# dsPIC_I2CMini.net
KiCad netlist of a schematic drawn in EAGLE
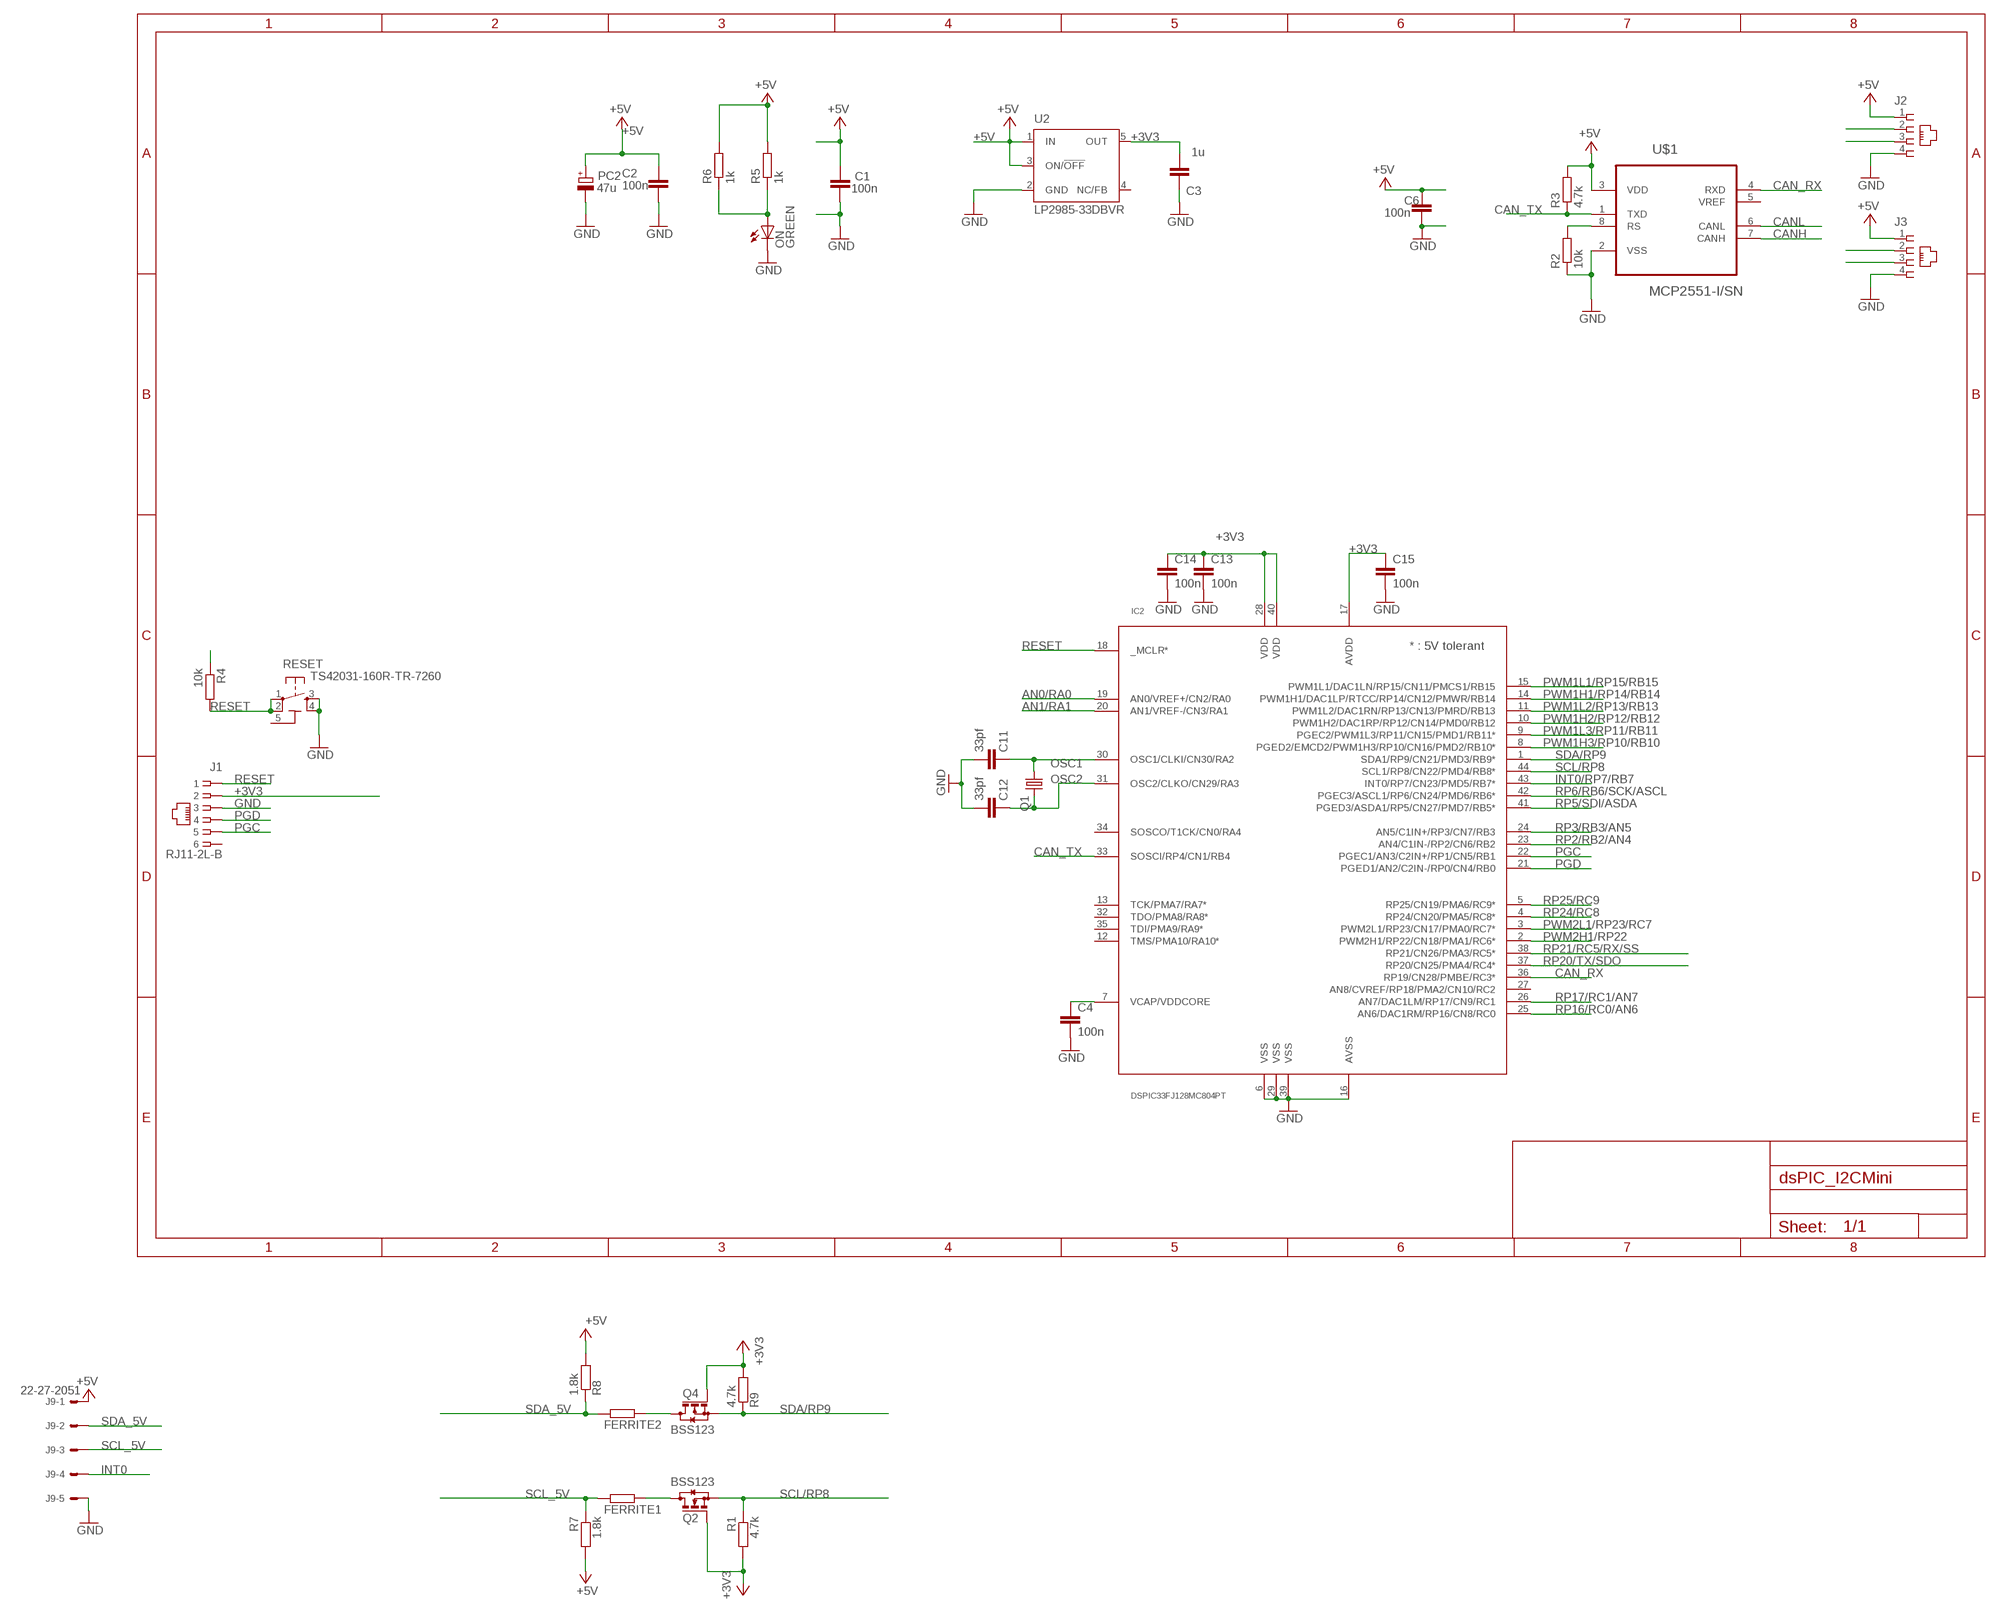
[diagram p0: schematic, sheet 1]

(export (version "E")
  (design (tool "Eeschema 10.0.6"))
  (components
    (comp (ref "C1")
      (value "100n")
      (footprint "eagle-import:C0603-ROUND")
      (libsource (lib "eagle-import") (part "C-EU0603-RND"))
    )
    (comp (ref "C2")
      (value "100n")
      (footprint "eagle-import:C0603-ROUND")
      (libsource (lib "eagle-import") (part "C-EU0603-RND"))
    )
    (comp (ref "C3")
      (value "1u")
      (footprint "eagle-import:C0603-ROUND")
      (libsource (lib "eagle-import") (part "C-EU0603-RND"))
    )
    (comp (ref "C4")
      (value "100n")
      (footprint "eagle-import:C0603K")
      (libsource (lib "eagle-import") (part "SmartPrj_C-EUC0603K"))
    )
    (comp (ref "C6")
      (value "100n")
      (footprint "eagle-import:C0603K")
      (libsource (lib "eagle-import") (part "SmartPrj_C-EUC0603K"))
    )
    (comp (ref "C11")
      (value "33pf")
      (footprint "eagle-import:C0603")
      (libsource (lib "eagle-import") (part "C-EUC0603"))
    )
    (comp (ref "C12")
      (value "33pf")
      (footprint "eagle-import:C0603")
      (libsource (lib "eagle-import") (part "C-EUC0603"))
    )
    (comp (ref "C13")
      (value "100n")
      (footprint "eagle-import:C0603")
      (libsource (lib "eagle-import") (part "C-EUC0603"))
    )
    (comp (ref "C14")
      (value "100n")
      (footprint "eagle-import:C0603")
      (libsource (lib "eagle-import") (part "C-EUC0603"))
    )
    (comp (ref "C15")
      (value "100n")
      (footprint "eagle-import:C0603")
      (libsource (lib "eagle-import") (part "C-EUC0603"))
    )
    (comp (ref "FERRITE1")
      (value "R-EU_M0805")
      (footprint "eagle-import:M0805")
      (libsource (lib "eagle-import") (part "R-EU_M0805"))
    )
    (comp (ref "FERRITE2")
      (value "R-EU_M0805")
      (footprint "eagle-import:M0805")
      (libsource (lib "eagle-import") (part "R-EU_M0805"))
    )
    (comp (ref "IC2")
      (value "DSPIC33FJ128MC804PT")
      (footprint "eagle-import:TQFP44")
      (libsource (lib "eagle-import") (part "DSPIC33F04PTJ128MC8"))
    )
    (comp (ref "J1")
      (value "RJ11-2L-B")
      (footprint "eagle-import:RJ11-NO_SHIELD")
      (fields (field (name "MF") "TYCO ELECTRONICS") (field (name "OC_FARNELL") "1393306"))
      (libsource (lib "eagle-import") (part "RJ11-2L-B"))
    )
    (comp (ref "J2")
      (value "520249-2")
      (footprint "eagle-import:520249-2")
      (libsource (lib "eagle-import") (part "520249-2"))
    )
    (comp (ref "J3")
      (value "520249-2")
      (footprint "eagle-import:520249-2")
      (libsource (lib "eagle-import") (part "520249-2"))
    )
    (comp (ref "J9")
      (value "22-27-2051")
      (footprint "eagle-import:6410-05")
      (libsource (lib "eagle-import") (part "22-?-0527-2051"))
    )
    (comp (ref "ON")
      (value "GREEN")
      (footprint "eagle-import:CHIP-LED0805")
      (libsource (lib "eagle-import") (part "LEDCHIP-LED0805"))
    )
    (comp (ref "PC2")
      (value "47u")
      (footprint "eagle-import:PANASONIC_D")
      (libsource (lib "eagle-import") (part "CPOL-EUD"))
    )
    (comp (ref "Q1")
      (value "CRYSTALSM49")
      (footprint "eagle-import:SM49")
      (fields (field (name "OC_FARNELL") "1842332"))
      (libsource (lib "eagle-import") (part "CRYSTALSM49"))
    )
    (comp (ref "Q2")
      (value "BSS123")
      (footprint "eagle-import:SOT23")
      (libsource (lib "eagle-import") (part "BSS123"))
    )
    (comp (ref "Q4")
      (value "BSS123")
      (footprint "eagle-import:SOT23")
      (libsource (lib "eagle-import") (part "BSS123"))
    )
    (comp (ref "R1")
      (value "4.7k")
      (footprint "eagle-import:R0805")
      (libsource (lib "eagle-import") (part "rcl_R-EU_R0805"))
    )
    (comp (ref "R2")
      (value "10k")
      (footprint "eagle-import:R0805")
      (libsource (lib "eagle-import") (part "R-EU_R0805"))
    )
    (comp (ref "R3")
      (value "4.7k")
      (footprint "eagle-import:R0805")
      (libsource (lib "eagle-import") (part "R-EU_R0805"))
    )
    (comp (ref "R4")
      (value "10k")
      (footprint "eagle-import:R0805")
      (libsource (lib "eagle-import") (part "R-EU_R0805"))
    )
    (comp (ref "R5")
      (value "1k")
      (footprint "eagle-import:R0805")
      (libsource (lib "eagle-import") (part "R-EU_R0805"))
    )
    (comp (ref "R6")
      (value "1k")
      (footprint "eagle-import:R0805")
      (libsource (lib "eagle-import") (part "R-EU_R0805"))
    )
    (comp (ref "R7")
      (value "1.8k")
      (footprint "eagle-import:R0805")
      (libsource (lib "eagle-import") (part "rcl_R-EU_R0805"))
    )
    (comp (ref "R8")
      (value "1.8k")
      (footprint "eagle-import:R0805")
      (libsource (lib "eagle-import") (part "rcl_R-EU_R0805"))
    )
    (comp (ref "R9")
      (value "4.7k")
      (footprint "eagle-import:R0805")
      (libsource (lib "eagle-import") (part "rcl_R-EU_R0805"))
    )
    (comp (ref "RESET")
      (value "TS42031-160R-TR-7260")
      (footprint "eagle-import:TS42")
      (libsource (lib "eagle-import") (part "TS42"))
    )
    (comp (ref "U$1")
      (value "MCP2551-I/SN")
      (footprint "eagle-import:SOIC127P600X175-8N")
      (libsource (lib "eagle-import") (part "MCP2551-I/SN"))
    )
    (comp (ref "U2")
      (value "LP2985-33DBVR")
      (footprint "eagle-import:SOT23-DBV")
      (libsource (lib "eagle-import") (part "LP2985-XXDBVR33"))
    )
  )
  (nets
    (net (code "1") (name "+3V3") (class "Default")
      (node (ref "C13") (pin "1") (pinfunction "1_1") (pintype "passive"))
      (node (ref "C14") (pin "1") (pinfunction "1_1") (pintype "passive"))
      (node (ref "C15") (pin "1") (pinfunction "1_1") (pintype "passive"))
      (node (ref "C3") (pin "2") (pinfunction "2_2") (pintype "passive"))
      (node (ref "IC2") (pin "17") (pinfunction "AVDD_17") (pintype "power_in"))
      (node (ref "IC2") (pin "28") (pinfunction "VDD_28") (pintype "power_in"))
      (node (ref "IC2") (pin "40") (pinfunction "VDD_40") (pintype "power_in"))
      (node (ref "J1") (pin "2") (pinfunction "2_2") (pintype "passive"))
      (node (ref "Q2") (pin "1") (pinfunction "G_1") (pintype "passive"))
      (node (ref "Q4") (pin "1") (pinfunction "G_1") (pintype "passive"))
      (node (ref "R1") (pin "2") (pinfunction "2_2") (pintype "passive"))
      (node (ref "R4") (pin "1") (pinfunction "1_1") (pintype "passive"))
      (node (ref "R9") (pin "2") (pinfunction "2_2") (pintype "passive"))
      (node (ref "U2") (pin "5") (pinfunction "OUT_5") (pintype "passive"))
    )
    (net (code "2") (name "+5V") (class "Default")
      (node (ref "C1") (pin "2") (pinfunction "2_2") (pintype "passive"))
      (node (ref "C2") (pin "2") (pinfunction "2_2") (pintype "passive"))
      (node (ref "C6") (pin "2") (pinfunction "2_2") (pintype "passive"))
      (node (ref "J2") (pin "1") (pinfunction "1_1") (pintype "passive"))
      (node (ref "J3") (pin "1") (pinfunction "1_1") (pintype "passive"))
      (node (ref "J9") (pin "1") (pinfunction "S_1") (pintype "passive"))
      (node (ref "PC2") (pin "+") (pinfunction "+_+") (pintype "passive"))
      (node (ref "R3") (pin "2") (pinfunction "2_2") (pintype "passive"))
      (node (ref "R5") (pin "2") (pinfunction "2_2") (pintype "passive"))
      (node (ref "R6") (pin "2") (pinfunction "2_2") (pintype "passive"))
      (node (ref "R7") (pin "2") (pinfunction "2_2") (pintype "passive"))
      (node (ref "R8") (pin "2") (pinfunction "2_2") (pintype "passive"))
      (node (ref "U$1") (pin "3") (pinfunction "VDD_3") (pintype "power_in"))
      (node (ref "U2") (pin "1") (pinfunction "IN_1") (pintype "input"))
      (node (ref "U2") (pin "3") (pinfunction "ON/~{OFF}_3") (pintype "input"))
    )
    (net (code "3") (name "/5-GND") (class "Default")
      (node (ref "RESET") (pin "5") (pinfunction "5-GND_5") (pintype "power_in"))
    )
    (net (code "4") (name "/AN0{slash}RA0") (class "Default")
      (node (ref "IC2") (pin "19") (pinfunction "AN0/VREF+/CN2/RA0_19") (pintype "bidirectional"))
    )
    (net (code "5") (name "/AN1{slash}RA1") (class "Default")
      (node (ref "IC2") (pin "20") (pinfunction "AN1/VREF-/CN3/RA1_20") (pintype "bidirectional"))
    )
    (net (code "6") (name "/CANH") (class "Default")
      (node (ref "J2") (pin "2") (pinfunction "2_2") (pintype "passive"))
      (node (ref "J3") (pin "2") (pinfunction "2_2") (pintype "passive"))
      (node (ref "U$1") (pin "7") (pinfunction "CANH_7") (pintype "bidirectional"))
    )
    (net (code "7") (name "/CANL") (class "Default")
      (node (ref "J2") (pin "3") (pinfunction "3_3") (pintype "passive"))
      (node (ref "J3") (pin "3") (pinfunction "3_3") (pintype "passive"))
      (node (ref "U$1") (pin "6") (pinfunction "CANL_6") (pintype "bidirectional"))
    )
    (net (code "8") (name "/CAN_RX") (class "Default")
      (node (ref "IC2") (pin "36") (pinfunction "RP19/CN28/PMBE/RC3*_36") (pintype "bidirectional"))
      (node (ref "U$1") (pin "4") (pinfunction "RXD_4") (pintype "output"))
    )
    (net (code "9") (name "/CAN_TX") (class "Default")
      (node (ref "IC2") (pin "33") (pinfunction "SOSCI/RP4/CN1/RB4_33") (pintype "bidirectional"))
      (node (ref "R3") (pin "1") (pinfunction "1_1") (pintype "passive"))
      (node (ref "U$1") (pin "1") (pinfunction "TXD_1") (pintype "input"))
    )
    (net (code "10") (name "/INT0") (class "Default")
      (node (ref "J9") (pin "4") (pinfunction "S_4") (pintype "passive"))
    )
    (net (code "11") (name "/INT0{slash}RP7{slash}RB7") (class "Default")
      (node (ref "IC2") (pin "43") (pinfunction "INT0/RP7/CN23/PMD5/RB7*_43") (pintype "bidirectional"))
    )
    (net (code "12") (name "/OSC1") (class "Default")
      (node (ref "C11") (pin "1") (pinfunction "1_1") (pintype "passive"))
      (node (ref "IC2") (pin "30") (pinfunction "OSC1/CLKI/CN30/RA2_30") (pintype "bidirectional"))
      (node (ref "Q1") (pin "1") (pinfunction "1_1") (pintype "passive"))
    )
    (net (code "13") (name "/OSC2") (class "Default")
      (node (ref "C12") (pin "1") (pinfunction "1_1") (pintype "passive"))
      (node (ref "IC2") (pin "31") (pinfunction "OSC2/CLKO/CN29/RA3_31") (pintype "bidirectional"))
      (node (ref "Q1") (pin "2") (pinfunction "2_2") (pintype "passive"))
    )
    (net (code "14") (name "/PGC") (class "Default")
      (node (ref "IC2") (pin "22") (pinfunction "PGEC1/AN3/C2IN+/RP1/CN5/RB1_22") (pintype "bidirectional"))
      (node (ref "J1") (pin "5") (pinfunction "5_5") (pintype "passive"))
    )
    (net (code "15") (name "/PGD") (class "Default")
      (node (ref "IC2") (pin "21") (pinfunction "PGED1/AN2/C2IN-/RP0/CN4/RB0_21") (pintype "bidirectional"))
      (node (ref "J1") (pin "4") (pinfunction "4_4") (pintype "passive"))
    )
    (net (code "16") (name "/PWM1H1{slash}RP14{slash}RB14") (class "Default")
      (node (ref "IC2") (pin "14") (pinfunction "PWM1H1/DAC1LP/RTCC/RP14/CN12/PMWR/RB14_14") (pintype "bidirectional"))
    )
    (net (code "17") (name "/PWM1H2{slash}RP12{slash}RB12") (class "Default")
      (node (ref "IC2") (pin "10") (pinfunction "PWM1H2/DAC1RP/RP12/CN14/PMD0/RB12_10") (pintype "bidirectional"))
    )
    (net (code "18") (name "/PWM1H3{slash}RP10{slash}RB10") (class "Default")
      (node (ref "IC2") (pin "8") (pinfunction "PGED2/EMCD2/PWM1H3/RP10/CN16/PMD2/RB10*_8") (pintype "bidirectional"))
    )
    (net (code "19") (name "/PWM1L1{slash}RP15{slash}RB15") (class "Default")
      (node (ref "IC2") (pin "15") (pinfunction "PWM1L1/DAC1LN/RP15/CN11/PMCS1/RB15_15") (pintype "bidirectional"))
    )
    (net (code "20") (name "/PWM1L2{slash}RP13{slash}RB13") (class "Default")
      (node (ref "IC2") (pin "11") (pinfunction "PWM1L2/DAC1RN/RP13/CN13/PMRD/RB13_11") (pintype "bidirectional"))
    )
    (net (code "21") (name "/PWM1L3{slash}RP11{slash}RB11") (class "Default")
      (node (ref "IC2") (pin "9") (pinfunction "PGEC2/PWM1L3/RP11/CN15/PMD1/RB11*_9") (pintype "bidirectional"))
    )
    (net (code "22") (name "/PWM2H1{slash}RP22") (class "Default")
      (node (ref "IC2") (pin "2") (pinfunction "PWM2H1/RP22/CN18/PMA1/RC6*_2") (pintype "bidirectional"))
    )
    (net (code "23") (name "/PWM2L1{slash}RP23{slash}RC7") (class "Default")
      (node (ref "IC2") (pin "3") (pinfunction "PWM2L1/RP23/CN17/PMA0/RC7*_3") (pintype "bidirectional"))
    )
    (net (code "24") (name "/RESET") (class "Default")
      (node (ref "IC2") (pin "18") (pinfunction "_MCLR*_18") (pintype "input"))
      (node (ref "J1") (pin "1") (pinfunction "1_1") (pintype "passive"))
      (node (ref "R4") (pin "2") (pinfunction "2_2") (pintype "passive"))
      (node (ref "RESET") (pin "1") (pinfunction "1_1") (pintype "passive"))
      (node (ref "RESET") (pin "2") (pinfunction "2_2") (pintype "passive"))
    )
    (net (code "25") (name "/RP2{slash}RB2{slash}AN4") (class "Default")
      (node (ref "IC2") (pin "23") (pinfunction "AN4/C1IN-/RP2/CN6/RB2_23") (pintype "bidirectional"))
    )
    (net (code "26") (name "/RP3{slash}RB3{slash}AN5") (class "Default")
      (node (ref "IC2") (pin "24") (pinfunction "AN5/C1IN+/RP3/CN7/RB3_24") (pintype "bidirectional"))
    )
    (net (code "27") (name "/RP5{slash}SDI{slash}ASDA") (class "Default")
      (node (ref "IC2") (pin "41") (pinfunction "PGED3/ASDA1/RP5/CN27/PMD7/RB5*_41") (pintype "bidirectional"))
    )
    (net (code "28") (name "/RP6{slash}RB6{slash}SCK{slash}ASCL") (class "Default")
      (node (ref "IC2") (pin "42") (pinfunction "PGEC3/ASCL1/RP6/CN24/PMD6/RB6*_42") (pintype "bidirectional"))
    )
    (net (code "29") (name "/RP16{slash}RC0{slash}AN6") (class "Default")
      (node (ref "IC2") (pin "25") (pinfunction "AN6/DAC1RM/RP16/CN8/RC0_25") (pintype "bidirectional"))
    )
    (net (code "30") (name "/RP17{slash}RC1{slash}AN7") (class "Default")
      (node (ref "IC2") (pin "26") (pinfunction "AN7/DAC1LM/RP17/CN9/RC1_26") (pintype "bidirectional"))
    )
    (net (code "31") (name "/RP20{slash}TX{slash}SDO") (class "Default")
      (node (ref "IC2") (pin "37") (pinfunction "RP20/CN25/PMA4/RC4*_37") (pintype "bidirectional"))
    )
    (net (code "32") (name "/RP21{slash}RC5{slash}RX{slash}SS") (class "Default")
      (node (ref "IC2") (pin "38") (pinfunction "RP21/CN26/PMA3/RC5*_38") (pintype "bidirectional"))
    )
    (net (code "33") (name "/RP24{slash}RC8") (class "Default")
      (node (ref "IC2") (pin "4") (pinfunction "RP24/CN20/PMA5/RC8*_4") (pintype "bidirectional"))
    )
    (net (code "34") (name "/RP25{slash}RC9") (class "Default")
      (node (ref "IC2") (pin "5") (pinfunction "RP25/CN19/PMA6/RC9*_5") (pintype "bidirectional"))
    )
    (net (code "35") (name "/SCL_5V") (class "Default")
      (node (ref "FERRITE1") (pin "1") (pinfunction "1_1") (pintype "passive"))
      (node (ref "J9") (pin "3") (pinfunction "S_3") (pintype "passive"))
      (node (ref "R7") (pin "1") (pinfunction "1_1") (pintype "passive"))
    )
    (net (code "36") (name "/SCL{slash}RP8") (class "Default")
      (node (ref "IC2") (pin "44") (pinfunction "SCL1/RP8/CN22/PMD4/RB8*_44") (pintype "bidirectional"))
      (node (ref "Q2") (pin "2") (pinfunction "S_2") (pintype "passive"))
      (node (ref "R1") (pin "1") (pinfunction "1_1") (pintype "passive"))
    )
    (net (code "37") (name "/SDA_5V") (class "Default")
      (node (ref "FERRITE2") (pin "1") (pinfunction "1_1") (pintype "passive"))
      (node (ref "J9") (pin "2") (pinfunction "S_2") (pintype "passive"))
      (node (ref "R8") (pin "1") (pinfunction "1_1") (pintype "passive"))
    )
    (net (code "38") (name "/SDA{slash}RP9") (class "Default")
      (node (ref "IC2") (pin "1") (pinfunction "SDA1/RP9/CN21/PMD3/RB9*_1") (pintype "bidirectional"))
      (node (ref "Q4") (pin "2") (pinfunction "S_2") (pintype "passive"))
      (node (ref "R9") (pin "1") (pinfunction "1_1") (pintype "passive"))
    )
    (net (code "39") (name "GND") (class "Default")
      (node (ref "C1") (pin "1") (pinfunction "1_1") (pintype "passive"))
      (node (ref "C11") (pin "2") (pinfunction "2_2") (pintype "passive"))
      (node (ref "C12") (pin "2") (pinfunction "2_2") (pintype "passive"))
      (node (ref "C13") (pin "2") (pinfunction "2_2") (pintype "passive"))
      (node (ref "C14") (pin "2") (pinfunction "2_2") (pintype "passive"))
      (node (ref "C15") (pin "2") (pinfunction "2_2") (pintype "passive"))
      (node (ref "C2") (pin "1") (pinfunction "1_1") (pintype "passive"))
      (node (ref "C3") (pin "1") (pinfunction "1_1") (pintype "passive"))
      (node (ref "C4") (pin "2") (pinfunction "2_2") (pintype "passive"))
      (node (ref "C6") (pin "1") (pinfunction "1_1") (pintype "passive"))
      (node (ref "IC2") (pin "16") (pinfunction "AVSS_16") (pintype "power_in"))
      (node (ref "IC2") (pin "29") (pinfunction "VSS_29") (pintype "power_in"))
      (node (ref "IC2") (pin "39") (pinfunction "VSS_39") (pintype "power_in"))
      (node (ref "IC2") (pin "6") (pinfunction "VSS_6") (pintype "power_in"))
      (node (ref "J1") (pin "3") (pinfunction "3_3") (pintype "passive"))
      (node (ref "J2") (pin "4") (pinfunction "4_4") (pintype "passive"))
      (node (ref "J3") (pin "4") (pinfunction "4_4") (pintype "passive"))
      (node (ref "J9") (pin "5") (pinfunction "S_5") (pintype "passive"))
      (node (ref "ON") (pin "C") (pinfunction "C_C") (pintype "passive"))
      (node (ref "PC2") (pin "-") (pinfunction "-_-") (pintype "passive"))
      (node (ref "R2") (pin "1") (pinfunction "1_1") (pintype "passive"))
      (node (ref "RESET") (pin "3") (pinfunction "3_3") (pintype "passive"))
      (node (ref "RESET") (pin "4") (pinfunction "4_4") (pintype "passive"))
      (node (ref "U$1") (pin "2") (pinfunction "VSS_2") (pintype "passive"))
      (node (ref "U2") (pin "2") (pinfunction "GND_2") (pintype "power_in"))
    )
    (net (code "40") (name "Net-(IC2-VCAP{slash}VDDCORE)") (class "Default")
      (node (ref "C4") (pin "1") (pinfunction "1_1") (pintype "passive"))
      (node (ref "IC2") (pin "7") (pinfunction "VCAP/VDDCORE_7") (pintype "power_in"))
    )
    (net (code "41") (name "Net-(ON-PadA)") (class "Default")
      (node (ref "ON") (pin "A") (pinfunction "A_A") (pintype "passive"))
      (node (ref "R5") (pin "1") (pinfunction "1_1") (pintype "passive"))
      (node (ref "R6") (pin "1") (pinfunction "1_1") (pintype "passive"))
    )
    (net (code "42") (name "Net-(Q2-D)") (class "Default")
      (node (ref "FERRITE1") (pin "2") (pinfunction "2_2") (pintype "passive"))
      (node (ref "Q2") (pin "3") (pinfunction "D_3") (pintype "passive"))
    )
    (net (code "43") (name "Net-(Q4-D)") (class "Default")
      (node (ref "FERRITE2") (pin "2") (pinfunction "2_2") (pintype "passive"))
      (node (ref "Q4") (pin "3") (pinfunction "D_3") (pintype "passive"))
    )
    (net (code "44") (name "Net-(U$1-RS)") (class "Default")
      (node (ref "R2") (pin "2") (pinfunction "2_2") (pintype "passive"))
      (node (ref "U$1") (pin "8") (pinfunction "RS_8") (pintype "input"))
    )
    (net (code "45") (name "unconnected-(IC2-AN8{slash}CVREF{slash}RP18{slash}PMA2{slash}CN10{slash}RC2-Pad27)") (class "Default")
      (node (ref "IC2") (pin "27") (pinfunction "AN8/CVREF/RP18/PMA2/CN10/RC2_27") (pintype "bidirectional"))
    )
    (net (code "46") (name "unconnected-(IC2-SOSCO{slash}T1CK{slash}CN0{slash}RA4-Pad34)") (class "Default")
      (node (ref "IC2") (pin "34") (pinfunction "SOSCO/T1CK/CN0/RA4_34") (pintype "bidirectional"))
    )
    (net (code "47") (name "unconnected-(IC2-TCK{slash}PMA7{slash}RA7*-Pad13)") (class "Default")
      (node (ref "IC2") (pin "13") (pinfunction "TCK/PMA7/RA7*_13") (pintype "bidirectional"))
    )
    (net (code "48") (name "unconnected-(IC2-TDI{slash}PMA9{slash}RA9*-Pad35)") (class "Default")
      (node (ref "IC2") (pin "35") (pinfunction "TDI/PMA9/RA9*_35") (pintype "bidirectional"))
    )
    (net (code "49") (name "unconnected-(IC2-TDO{slash}PMA8{slash}RA8*-Pad32)") (class "Default")
      (node (ref "IC2") (pin "32") (pinfunction "TDO/PMA8/RA8*_32") (pintype "bidirectional"))
    )
    (net (code "50") (name "unconnected-(IC2-TMS{slash}PMA10{slash}RA10*-Pad12)") (class "Default")
      (node (ref "IC2") (pin "12") (pinfunction "TMS/PMA10/RA10*_12") (pintype "bidirectional"))
    )
    (net (code "51") (name "unconnected-(J1-Pad6)") (class "Default")
      (node (ref "J1") (pin "6") (pinfunction "6_6") (pintype "passive"))
    )
    (net (code "52") (name "unconnected-(U$1-VREF-Pad5)") (class "Default")
      (node (ref "U$1") (pin "5") (pinfunction "VREF_5") (pintype "output"))
    )
    (net (code "53") (name "unconnected-(U2-NC{slash}FB-Pad4)") (class "Default")
      (node (ref "U2") (pin "4") (pinfunction "NC/FB_4") (pintype "passive"))
    )
  )
)
